# EEZ_DIB_PREL6_r1B1.net
KiCad netlist of a schematic drawn in EAGLE
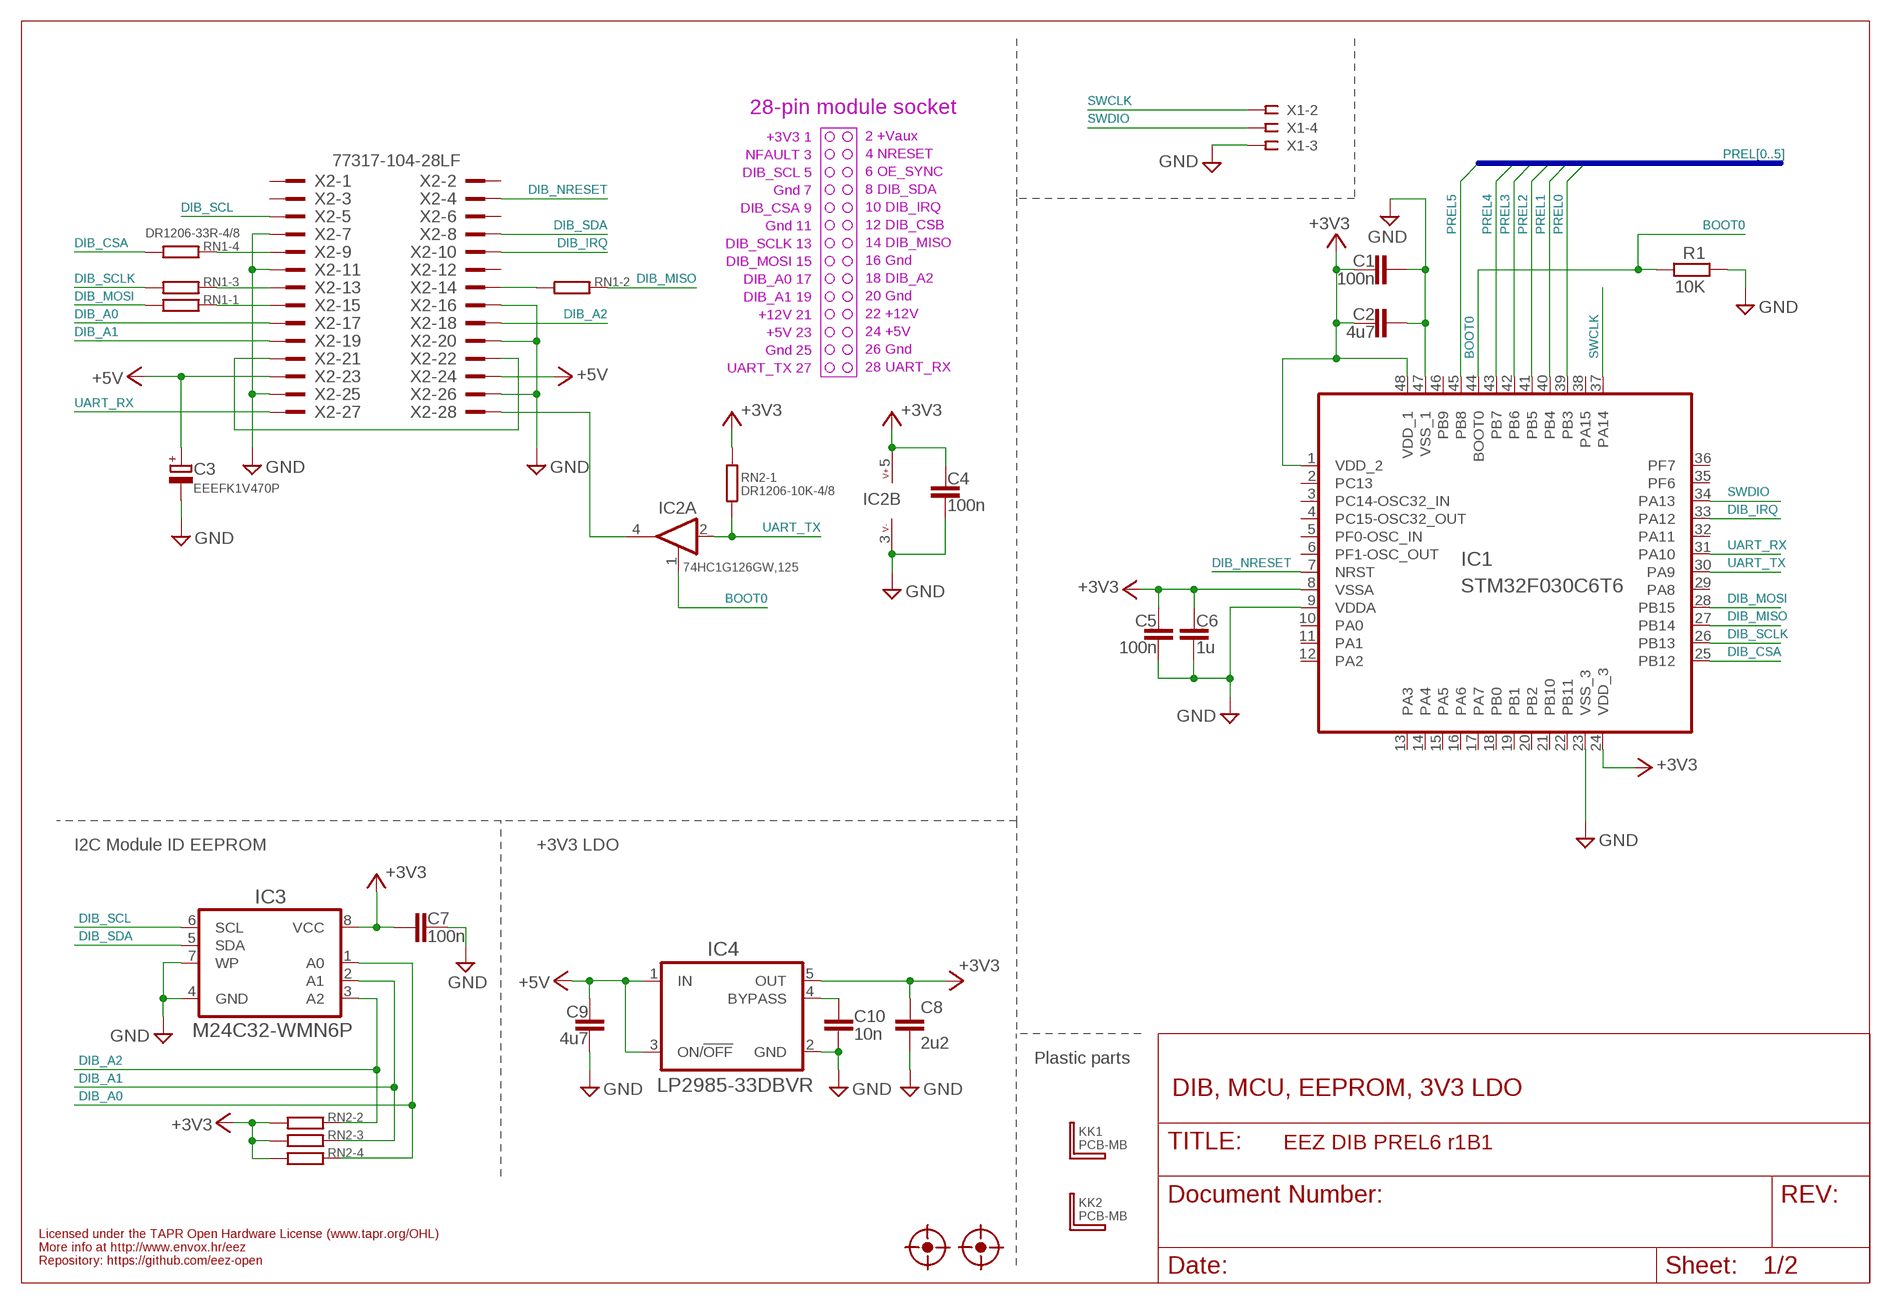
[diagram p0: schematic, sheet 1]
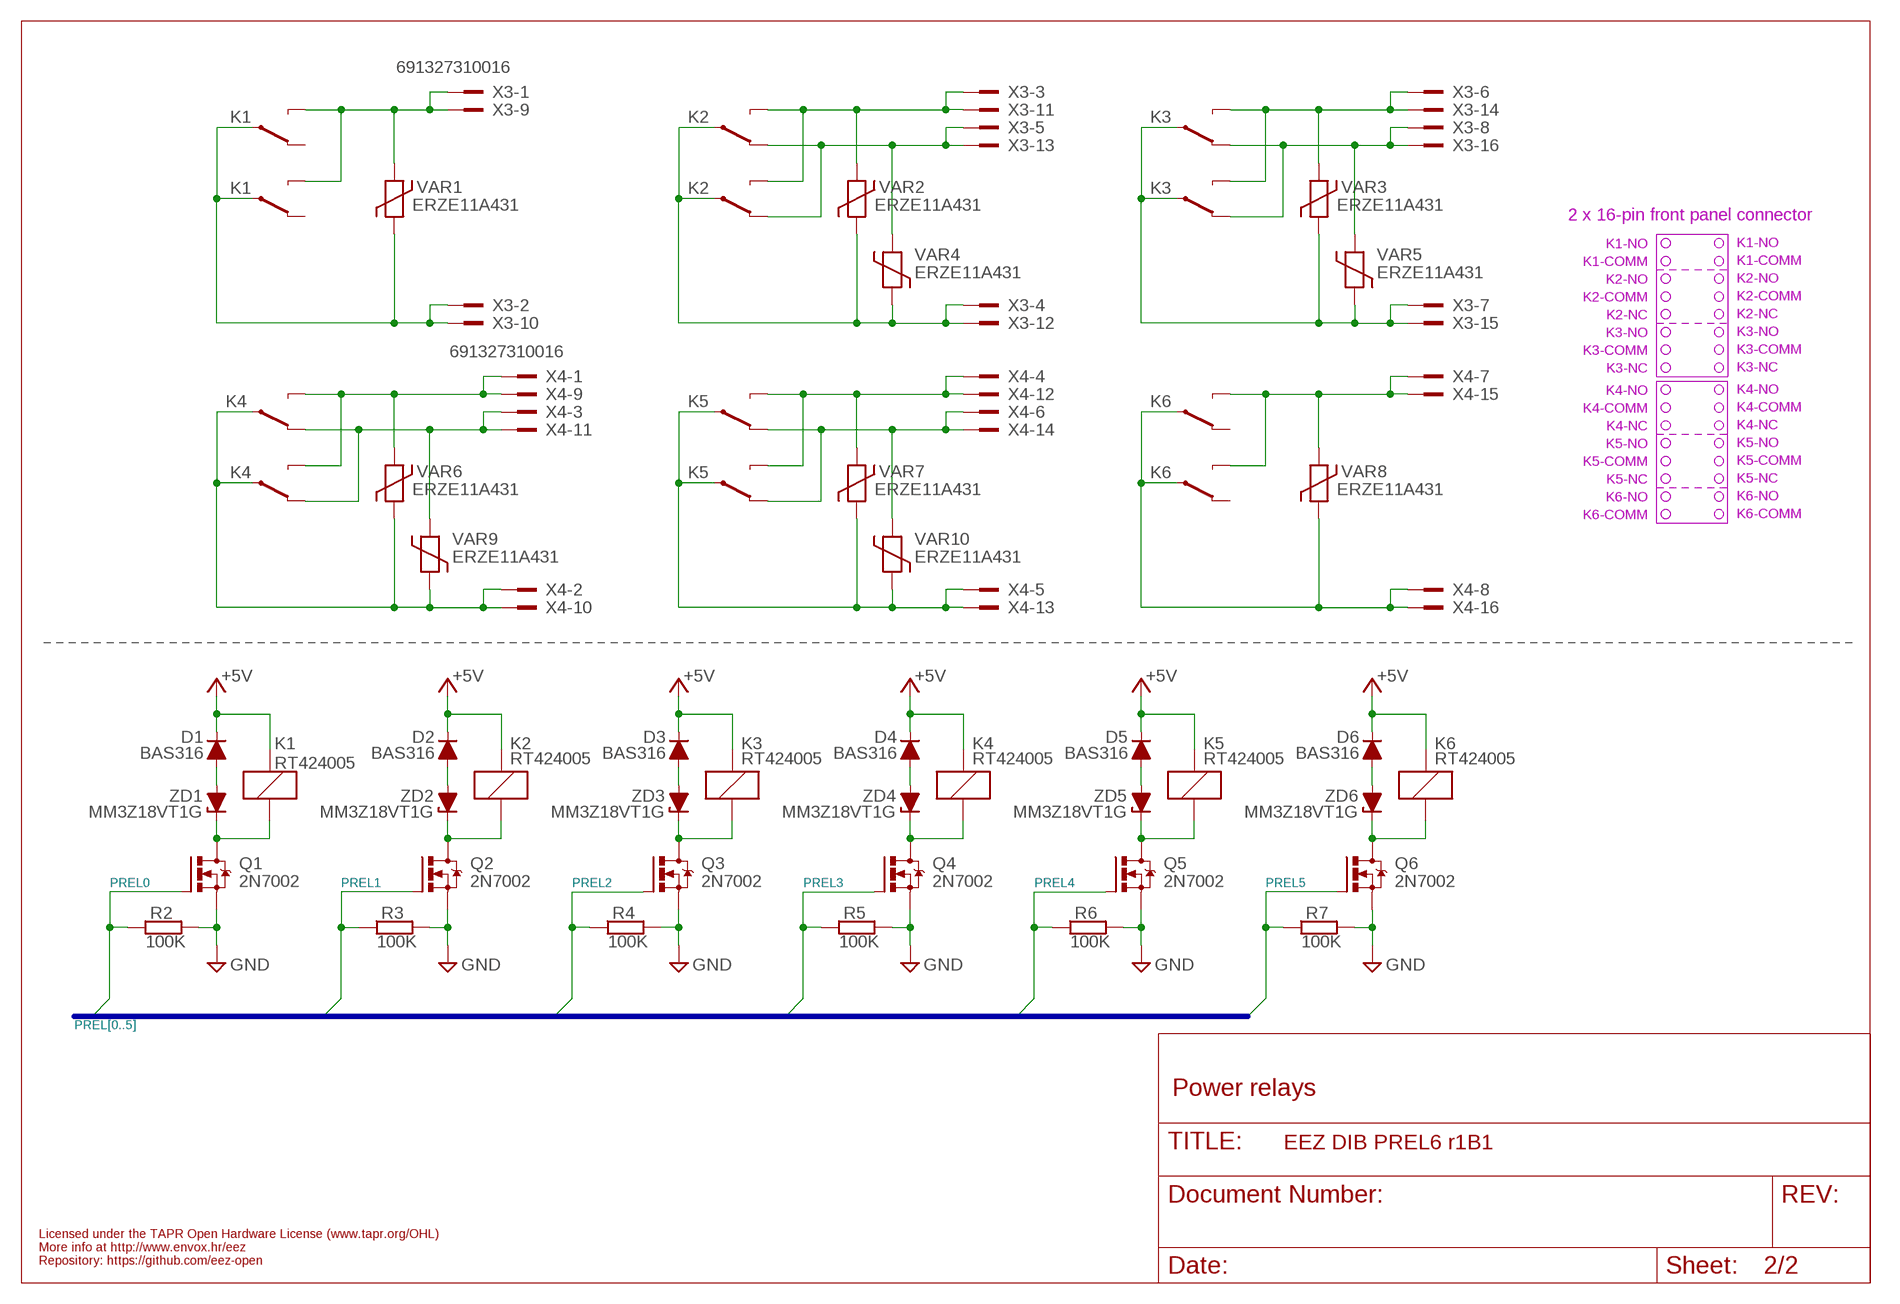
[diagram p1: schematic, sheet 2]

(export (version "E")
  (design (tool "Eeschema 10.0.6"))
  (components
    (comp (ref "D1")
      (value "BAS316")
      (footprint "eagle-import:SOD323-R")
      (libsource (lib "eagle-import") (part "DIODESOD323R"))
    )
    (comp (ref "D2")
      (value "BAS316")
      (footprint "eagle-import:SOD323-R")
      (libsource (lib "eagle-import") (part "DIODESOD323R"))
    )
    (comp (ref "D3")
      (value "BAS316")
      (footprint "eagle-import:SOD323-R")
      (libsource (lib "eagle-import") (part "DIODESOD323R"))
    )
    (comp (ref "D4")
      (value "BAS316")
      (footprint "eagle-import:SOD323-R")
      (libsource (lib "eagle-import") (part "DIODESOD323R"))
    )
    (comp (ref "D5")
      (value "BAS316")
      (footprint "eagle-import:SOD323-R")
      (libsource (lib "eagle-import") (part "DIODESOD323R"))
    )
    (comp (ref "D6")
      (value "BAS316")
      (footprint "eagle-import:SOD323-R")
      (libsource (lib "eagle-import") (part "DIODESOD323R"))
    )
    (comp (ref "K1")
      (value "RT424005")
      (footprint "eagle-import:RT-C_016A5_ROUND")
      (libsource (lib "eagle-import") (part "RELAY_RT314012-2"))
    )
    (comp (ref "K2")
      (value "RT424005")
      (footprint "eagle-import:RT-C_016A5_ROUND")
      (libsource (lib "eagle-import") (part "RELAY_RT314012-2"))
    )
    (comp (ref "K3")
      (value "RT424005")
      (footprint "eagle-import:RT-C_016A5_ROUND")
      (libsource (lib "eagle-import") (part "RELAY_RT314012-2"))
    )
    (comp (ref "K4")
      (value "RT424005")
      (footprint "eagle-import:RT-C_016A5_ROUND")
      (libsource (lib "eagle-import") (part "RELAY_RT314012-2"))
    )
    (comp (ref "K5")
      (value "RT424005")
      (footprint "eagle-import:RT-C_016A5_ROUND")
      (libsource (lib "eagle-import") (part "RELAY_RT314012-2"))
    )
    (comp (ref "K6")
      (value "RT424005")
      (footprint "eagle-import:RT-C_016A5_ROUND")
      (libsource (lib "eagle-import") (part "RELAY_RT314012-2"))
    )
    (comp (ref "Q1")
      (value "2N7002")
      (footprint "eagle-import:SOT103P240X110-3N")
      (fields
        (field (name "MPN") "2N7002-7-F")
        (field (name "MPN_1") "2N7002-7-F")
        (field (name "OC_FARNELL") "1713823")
        (field (name "OC_NEWARK") "25R5679")
        (field (name "PACKAGE") "SOT-23-3")
        (field (name "SUPPLIER") "DIODES INC.")
      )
      (libsource (lib "eagle-import") (part "2N7002"))
    )
    (comp (ref "Q2")
      (value "2N7002")
      (footprint "eagle-import:SOT103P240X110-3N")
      (fields
        (field (name "MPN") "2N7002-7-F")
        (field (name "MPN_1") "2N7002-7-F")
        (field (name "OC_FARNELL") "1713823")
        (field (name "OC_NEWARK") "25R5679")
        (field (name "PACKAGE") "SOT-23-3")
        (field (name "SUPPLIER") "DIODES INC.")
      )
      (libsource (lib "eagle-import") (part "2N7002"))
    )
    (comp (ref "Q3")
      (value "2N7002")
      (footprint "eagle-import:SOT103P240X110-3N")
      (fields
        (field (name "MPN") "2N7002-7-F")
        (field (name "MPN_1") "2N7002-7-F")
        (field (name "OC_FARNELL") "1713823")
        (field (name "OC_NEWARK") "25R5679")
        (field (name "PACKAGE") "SOT-23-3")
        (field (name "SUPPLIER") "DIODES INC.")
      )
      (libsource (lib "eagle-import") (part "2N7002"))
    )
    (comp (ref "Q4")
      (value "2N7002")
      (footprint "eagle-import:SOT103P240X110-3N")
      (fields
        (field (name "MPN") "2N7002-7-F")
        (field (name "MPN_1") "2N7002-7-F")
        (field (name "OC_FARNELL") "1713823")
        (field (name "OC_NEWARK") "25R5679")
        (field (name "PACKAGE") "SOT-23-3")
        (field (name "SUPPLIER") "DIODES INC.")
      )
      (libsource (lib "eagle-import") (part "2N7002"))
    )
    (comp (ref "Q5")
      (value "2N7002")
      (footprint "eagle-import:SOT103P240X110-3N")
      (fields
        (field (name "MPN") "2N7002-7-F")
        (field (name "MPN_1") "2N7002-7-F")
        (field (name "OC_FARNELL") "1713823")
        (field (name "OC_NEWARK") "25R5679")
        (field (name "PACKAGE") "SOT-23-3")
        (field (name "SUPPLIER") "DIODES INC.")
      )
      (libsource (lib "eagle-import") (part "2N7002"))
    )
    (comp (ref "Q6")
      (value "2N7002")
      (footprint "eagle-import:SOT103P240X110-3N")
      (fields
        (field (name "MPN") "2N7002-7-F")
        (field (name "MPN_1") "2N7002-7-F")
        (field (name "OC_FARNELL") "1713823")
        (field (name "OC_NEWARK") "25R5679")
        (field (name "PACKAGE") "SOT-23-3")
        (field (name "SUPPLIER") "DIODES INC.")
      )
      (libsource (lib "eagle-import") (part "2N7002"))
    )
    (comp (ref "R2")
      (value "100K")
      (footprint "eagle-import:R0805")
      (libsource (lib "eagle-import") (part "R-EU_R0805"))
    )
    (comp (ref "R3")
      (value "100K")
      (footprint "eagle-import:R0805")
      (libsource (lib "eagle-import") (part "R-EU_R0805"))
    )
    (comp (ref "R4")
      (value "100K")
      (footprint "eagle-import:R0805")
      (libsource (lib "eagle-import") (part "R-EU_R0805"))
    )
    (comp (ref "R5")
      (value "100K")
      (footprint "eagle-import:R0805")
      (libsource (lib "eagle-import") (part "R-EU_R0805"))
    )
    (comp (ref "R6")
      (value "100K")
      (footprint "eagle-import:R0805")
      (libsource (lib "eagle-import") (part "R-EU_R0805"))
    )
    (comp (ref "R7")
      (value "100K")
      (footprint "eagle-import:R0805")
      (libsource (lib "eagle-import") (part "R-EU_R0805"))
    )
    (comp (ref "VAR1")
      (value "ERZE11A431")
      (footprint "eagle-import:VARISTOR_13MM")
      (libsource (lib "eagle-import") (part "VARISTOR-13"))
    )
    (comp (ref "VAR2")
      (value "ERZE11A431")
      (footprint "eagle-import:VARISTOR_13MM")
      (libsource (lib "eagle-import") (part "VARISTOR-13"))
    )
    (comp (ref "VAR3")
      (value "ERZE11A431")
      (footprint "eagle-import:VARISTOR_13MM")
      (libsource (lib "eagle-import") (part "VARISTOR-13"))
    )
    (comp (ref "VAR4")
      (value "ERZE11A431")
      (footprint "eagle-import:VARISTOR_13MM")
      (libsource (lib "eagle-import") (part "VARISTOR-13"))
    )
    (comp (ref "VAR5")
      (value "ERZE11A431")
      (footprint "eagle-import:VARISTOR_13MM")
      (libsource (lib "eagle-import") (part "VARISTOR-13"))
    )
    (comp (ref "VAR6")
      (value "ERZE11A431")
      (footprint "eagle-import:VARISTOR_13MM")
      (libsource (lib "eagle-import") (part "VARISTOR-13"))
    )
    (comp (ref "VAR7")
      (value "ERZE11A431")
      (footprint "eagle-import:VARISTOR_13MM")
      (libsource (lib "eagle-import") (part "VARISTOR-13"))
    )
    (comp (ref "VAR8")
      (value "ERZE11A431")
      (footprint "eagle-import:VARISTOR_13MM")
      (libsource (lib "eagle-import") (part "VARISTOR-13"))
    )
    (comp (ref "VAR9")
      (value "ERZE11A431")
      (footprint "eagle-import:VARISTOR_13MM")
      (libsource (lib "eagle-import") (part "VARISTOR-13"))
    )
    (comp (ref "VAR10")
      (value "ERZE11A431")
      (footprint "eagle-import:VARISTOR_13MM")
      (libsource (lib "eagle-import") (part "VARISTOR-13"))
    )
    (comp (ref "X3")
      (value "691327310016")
      (footprint "eagle-import:691327310016")
      (libsource (lib "eagle-import") (part "691327310016"))
    )
    (comp (ref "X4")
      (value "691327310016")
      (footprint "eagle-import:691327310016")
      (libsource (lib "eagle-import") (part "691327310016"))
    )
    (comp (ref "ZD1")
      (value "MM3Z18VT1G")
      (footprint "eagle-import:SOD323-R")
      (libsource (lib "eagle-import") (part "ZENER-DIODESOD323R"))
    )
    (comp (ref "ZD2")
      (value "MM3Z18VT1G")
      (footprint "eagle-import:SOD323-R")
      (libsource (lib "eagle-import") (part "ZENER-DIODESOD323R"))
    )
    (comp (ref "ZD3")
      (value "MM3Z18VT1G")
      (footprint "eagle-import:SOD323-R")
      (libsource (lib "eagle-import") (part "ZENER-DIODESOD323R"))
    )
    (comp (ref "ZD4")
      (value "MM3Z18VT1G")
      (footprint "eagle-import:SOD323-R")
      (libsource (lib "eagle-import") (part "ZENER-DIODESOD323R"))
    )
    (comp (ref "ZD5")
      (value "MM3Z18VT1G")
      (footprint "eagle-import:SOD323-R")
      (libsource (lib "eagle-import") (part "ZENER-DIODESOD323R"))
    )
    (comp (ref "ZD6")
      (value "MM3Z18VT1G")
      (footprint "eagle-import:SOD323-R")
      (libsource (lib "eagle-import") (part "ZENER-DIODESOD323R"))
    )
    (comp (ref "C1")
      (value "100n")
      (footprint "eagle-import:C0603")
      (libsource (lib "eagle-import") (part "C-EUC0603"))
    )
    (comp (ref "C2")
      (value "4u7")
      (footprint "eagle-import:C1206")
      (libsource (lib "eagle-import") (part "C-EUC1206"))
    )
    (comp (ref "C3")
      (value "EEEFK1V470P")
      (footprint "eagle-import:CAPAE660X610N")
      (libsource (lib "eagle-import") (part "ECAPPANASONIC_H"))
    )
    (comp (ref "C4")
      (value "100n")
      (footprint "eagle-import:C0603")
      (libsource (lib "eagle-import") (part "C-EUC0603"))
    )
    (comp (ref "C5")
      (value "100n")
      (footprint "eagle-import:C0603")
      (libsource (lib "eagle-import") (part "C-EUC0603"))
    )
    (comp (ref "C6")
      (value "1u")
      (footprint "eagle-import:C0805")
      (libsource (lib "eagle-import") (part "C-EUC0805"))
    )
    (comp (ref "C7")
      (value "100n")
      (footprint "eagle-import:C0603")
      (libsource (lib "eagle-import") (part "C-EUC0603"))
    )
    (comp (ref "C8")
      (value "2u2")
      (footprint "eagle-import:C1206")
      (libsource (lib "eagle-import") (part "C-EUC1206"))
    )
    (comp (ref "C9")
      (value "4u7")
      (footprint "eagle-import:C1206")
      (libsource (lib "eagle-import") (part "C-EUC1206"))
    )
    (comp (ref "C10")
      (value "10n")
      (footprint "eagle-import:C0805")
      (libsource (lib "eagle-import") (part "C-EUC0805"))
    )
    (comp (ref "FM1")
      (value "FIDUCIAL_2")
      (footprint "eagle-import:FIDUCIAL_DUAL")
      (libsource (lib "eagle-import") (part "FIDUCIAL_2"))
    )
    (comp (ref "FM2")
      (value "FIDUCIAL_2")
      (footprint "eagle-import:FIDUCIAL_DUAL")
      (libsource (lib "eagle-import") (part "FIDUCIAL_2"))
    )
    (comp (ref "IC1")
      (value "STM32F030C6T6")
      (footprint "eagle-import:LQFP-48")
      (libsource (lib "eagle-import") (part "STM32F030C6T6"))
    )
    (comp (ref "IC2")
      (value "74HC1G126GW,125")
      (footprint "eagle-import:SOT65P210X110-5N")
      (libsource (lib "eagle-import") (part "74HC1G126GW,125"))
    )
    (comp (ref "IC3")
      (value "M24C32-WMN6P")
      (footprint "eagle-import:SOIC127P600X173-8N")
      (libsource (lib "eagle-import") (part "AT24CXXSOIC8"))
    )
    (comp (ref "IC4")
      (value "LP2985-33DBVR")
      (footprint "eagle-import:SOT95P270X145-5N")
      (libsource (lib "eagle-import") (part "LP2985"))
    )
    (comp (ref "KK1")
      (value "PCB-MB")
      (footprint "eagle-import:PCB-MB")
      (libsource (lib "eagle-import") (part "PCB-MB"))
    )
    (comp (ref "KK2")
      (value "PCB-MB")
      (footprint "eagle-import:PCB-MB")
      (libsource (lib "eagle-import") (part "PCB-MB"))
    )
    (comp (ref "R1")
      (value "10K")
      (footprint "eagle-import:R0805")
      (libsource (lib "eagle-import") (part "R-EU_R0805"))
    )
    (comp (ref "RN1")
      (value "DR1206-33R-4/8")
      (footprint "eagle-import:CAY16")
      (libsource (lib "eagle-import") (part "R_ARRAY4"))
    )
    (comp (ref "RN2")
      (value "DR1206-10K-4/8")
      (footprint "eagle-import:CAY16")
      (libsource (lib "eagle-import") (part "R_ARRAY4"))
    )
    (comp (ref "X1")
      (value "SSW-106-02-S-S")
      (footprint "eagle-import:SSW-106-02-S-S")
      (libsource (lib "eagle-import") (part "SSW-106-02-S-S"))
    )
    (comp (ref "X2")
      (value "77317-104-28LF")
      (footprint "eagle-import:77317-104-28LF")
      (libsource (lib "eagle-import") (part "77317-104-28LF"))
    )
  )
  (nets
    (net (code "1") (name "+3V3") (class "Default")
      (node (ref "C1") (pin "2") (pinfunction "2_2") (pintype "passive"))
      (node (ref "C2") (pin "1") (pinfunction "1_1") (pintype "passive"))
      (node (ref "C4") (pin "1") (pinfunction "1_1") (pintype "passive"))
      (node (ref "C5") (pin "1") (pinfunction "1_1") (pintype "passive"))
      (node (ref "C6") (pin "2") (pinfunction "2_2") (pintype "passive"))
      (node (ref "C7") (pin "2") (pinfunction "2_2") (pintype "passive"))
      (node (ref "C8") (pin "1") (pinfunction "1_1") (pintype "passive"))
      (node (ref "IC1") (pin "1") (pinfunction "VDD_2_1") (pintype "passive"))
      (node (ref "IC1") (pin "24") (pinfunction "VDD_3_24") (pintype "passive"))
      (node (ref "IC1") (pin "48") (pinfunction "VDD_1_48") (pintype "passive"))
      (node (ref "IC1") (pin "8") (pinfunction "VSSA_8") (pintype "passive"))
      (node (ref "IC2") (pin "5") (pinfunction "V+_5") (pintype "power_in"))
      (node (ref "IC3") (pin "8") (pinfunction "VCC_8") (pintype "power_in"))
      (node (ref "IC4") (pin "5") (pinfunction "OUT_5") (pintype "passive"))
      (node (ref "RN2") (pin "5") (pinfunction "2_5") (pintype "passive"))
      (node (ref "RN2") (pin "6") (pinfunction "2_6") (pintype "passive"))
      (node (ref "RN2") (pin "7") (pinfunction "2_7") (pintype "passive"))
      (node (ref "RN2") (pin "8") (pinfunction "2_8") (pintype "passive"))
    )
    (net (code "2") (name "+5V") (class "Default")
      (node (ref "C3") (pin "1") (pinfunction "+_1") (pintype "passive"))
      (node (ref "C9") (pin "2") (pinfunction "2_2") (pintype "passive"))
      (node (ref "D1") (pin "C") (pinfunction "C_C") (pintype "passive"))
      (node (ref "D2") (pin "C") (pinfunction "C_C") (pintype "passive"))
      (node (ref "D3") (pin "C") (pinfunction "C_C") (pintype "passive"))
      (node (ref "D4") (pin "C") (pinfunction "C_C") (pintype "passive"))
      (node (ref "D5") (pin "C") (pinfunction "C_C") (pintype "passive"))
      (node (ref "D6") (pin "C") (pinfunction "C_C") (pintype "passive"))
      (node (ref "IC4") (pin "1") (pinfunction "IN_1") (pintype "input"))
      (node (ref "IC4") (pin "3") (pinfunction "ON/~{OFF}_3") (pintype "input"))
      (node (ref "K1") (pin "A2") (pinfunction "C1_A2") (pintype "passive"))
      (node (ref "K2") (pin "A2") (pinfunction "C1_A2") (pintype "passive"))
      (node (ref "K3") (pin "A2") (pinfunction "C1_A2") (pintype "passive"))
      (node (ref "K4") (pin "A2") (pinfunction "C1_A2") (pintype "passive"))
      (node (ref "K5") (pin "A2") (pinfunction "C1_A2") (pintype "passive"))
      (node (ref "K6") (pin "A2") (pinfunction "C1_A2") (pintype "passive"))
      (node (ref "X2") (pin "23") (pinfunction "1_23") (pintype "passive"))
      (node (ref "X2") (pin "24") (pinfunction "1_24") (pintype "passive"))
    )
    (net (code "5") (name "BOOT0") (class "Default")
      (node (ref "IC1") (pin "44") (pinfunction "BOOT0_44") (pintype "input"))
      (node (ref "IC2") (pin "1") (pinfunction "EN_1") (pintype "input"))
      (node (ref "R1") (pin "2") (pinfunction "2_2") (pintype "passive"))
    )
    (net (code "6") (name "DIB_A0") (class "Default")
      (node (ref "IC3") (pin "1") (pinfunction "A0_1") (pintype "input"))
      (node (ref "RN2") (pin "4") (pinfunction "1_4") (pintype "passive"))
      (node (ref "X2") (pin "17") (pinfunction "1_17") (pintype "passive"))
    )
    (net (code "7") (name "DIB_A1") (class "Default")
      (node (ref "IC3") (pin "2") (pinfunction "A1_2") (pintype "input"))
      (node (ref "RN2") (pin "3") (pinfunction "1_3") (pintype "passive"))
      (node (ref "X2") (pin "19") (pinfunction "1_19") (pintype "passive"))
    )
    (net (code "8") (name "DIB_A2") (class "Default")
      (node (ref "IC3") (pin "3") (pinfunction "A2_3") (pintype "input"))
      (node (ref "RN2") (pin "2") (pinfunction "1_2") (pintype "passive"))
      (node (ref "X2") (pin "18") (pinfunction "1_18") (pintype "passive"))
    )
    (net (code "9") (name "DIB_CSA") (class "Default")
      (node (ref "IC1") (pin "25") (pinfunction "PB12_25") (pintype "bidirectional"))
      (node (ref "RN1") (pin "4") (pinfunction "1_4") (pintype "passive"))
    )
    (net (code "10") (name "DIB_IRQ") (class "Default")
      (node (ref "IC1") (pin "33") (pinfunction "PA12_33") (pintype "bidirectional"))
      (node (ref "X2") (pin "10") (pinfunction "1_10") (pintype "passive"))
    )
    (net (code "11") (name "DIB_MISO") (class "Default")
      (node (ref "IC1") (pin "27") (pinfunction "PB14_27") (pintype "bidirectional"))
      (node (ref "RN1") (pin "2") (pinfunction "1_2") (pintype "passive"))
    )
    (net (code "12") (name "DIB_MOSI") (class "Default")
      (node (ref "IC1") (pin "28") (pinfunction "PB15_28") (pintype "bidirectional"))
      (node (ref "RN1") (pin "1") (pinfunction "1_1") (pintype "passive"))
    )
    (net (code "13") (name "DIB_NRESET") (class "Default")
      (node (ref "IC1") (pin "7") (pinfunction "NRST_7") (pintype "input"))
      (node (ref "X2") (pin "4") (pinfunction "1_4") (pintype "passive"))
    )
    (net (code "14") (name "DIB_SCL") (class "Default")
      (node (ref "IC3") (pin "6") (pinfunction "SCL_6") (pintype "bidirectional"))
      (node (ref "X2") (pin "5") (pinfunction "1_5") (pintype "passive"))
    )
    (net (code "15") (name "DIB_SCLK") (class "Default")
      (node (ref "IC1") (pin "26") (pinfunction "PB13_26") (pintype "bidirectional"))
      (node (ref "RN1") (pin "3") (pinfunction "1_3") (pintype "passive"))
    )
    (net (code "16") (name "DIB_SDA") (class "Default")
      (node (ref "IC3") (pin "5") (pinfunction "SDA_5") (pintype "bidirectional"))
      (node (ref "X2") (pin "8") (pinfunction "1_8") (pintype "passive"))
    )
    (net (code "17") (name "GND") (class "Default")
      (node (ref "C1") (pin "1") (pinfunction "1_1") (pintype "passive"))
      (node (ref "C10") (pin "1") (pinfunction "1_1") (pintype "passive"))
      (node (ref "C2") (pin "2") (pinfunction "2_2") (pintype "passive"))
      (node (ref "C3") (pin "2") (pinfunction "-_2") (pintype "passive"))
      (node (ref "C4") (pin "2") (pinfunction "2_2") (pintype "passive"))
      (node (ref "C5") (pin "2") (pinfunction "2_2") (pintype "passive"))
      (node (ref "C6") (pin "1") (pinfunction "1_1") (pintype "passive"))
      (node (ref "C7") (pin "1") (pinfunction "1_1") (pintype "passive"))
      (node (ref "C8") (pin "2") (pinfunction "2_2") (pintype "passive"))
      (node (ref "C9") (pin "1") (pinfunction "1_1") (pintype "passive"))
      (node (ref "IC1") (pin "23") (pinfunction "VSS_3_23") (pintype "passive"))
      (node (ref "IC1") (pin "47") (pinfunction "VSS_1_47") (pintype "passive"))
      (node (ref "IC1") (pin "9") (pinfunction "VDDA_9") (pintype "passive"))
      (node (ref "IC2") (pin "3") (pinfunction "V-_3") (pintype "power_in"))
      (node (ref "IC3") (pin "4") (pinfunction "GND_4") (pintype "passive"))
      (node (ref "IC3") (pin "7") (pinfunction "WP_7") (pintype "input"))
      (node (ref "IC4") (pin "2") (pinfunction "GND_2") (pintype "passive"))
      (node (ref "Q1") (pin "2") (pinfunction "S_2") (pintype "passive"))
      (node (ref "Q2") (pin "2") (pinfunction "S_2") (pintype "passive"))
      (node (ref "Q3") (pin "2") (pinfunction "S_2") (pintype "passive"))
      (node (ref "Q4") (pin "2") (pinfunction "S_2") (pintype "passive"))
      (node (ref "Q5") (pin "2") (pinfunction "S_2") (pintype "passive"))
      (node (ref "Q6") (pin "2") (pinfunction "S_2") (pintype "passive"))
      (node (ref "R1") (pin "1") (pinfunction "1_1") (pintype "passive"))
      (node (ref "R2") (pin "2") (pinfunction "2_2") (pintype "passive"))
      (node (ref "R3") (pin "2") (pinfunction "2_2") (pintype "passive"))
      (node (ref "R4") (pin "2") (pinfunction "2_2") (pintype "passive"))
      (node (ref "R5") (pin "2") (pinfunction "2_2") (pintype "passive"))
      (node (ref "R6") (pin "2") (pinfunction "2_2") (pintype "passive"))
      (node (ref "R7") (pin "2") (pinfunction "2_2") (pintype "passive"))
      (node (ref "X1") (pin "3") (pinfunction "1_3") (pintype "passive"))
      (node (ref "X2") (pin "11") (pinfunction "1_11") (pintype "passive"))
      (node (ref "X2") (pin "16") (pinfunction "1_16") (pintype "passive"))
      (node (ref "X2") (pin "20") (pinfunction "1_20") (pintype "passive"))
      (node (ref "X2") (pin "25") (pinfunction "1_25") (pintype "passive"))
      (node (ref "X2") (pin "26") (pinfunction "1_26") (pintype "passive"))
      (node (ref "X2") (pin "7") (pinfunction "1_7") (pintype "passive"))
    )
    (net (code "18") (name "Net-(D1-PadA)") (class "Default")
      (node (ref "D1") (pin "A") (pinfunction "A_A") (pintype "passive"))
      (node (ref "ZD1") (pin "A") (pinfunction "A_A") (pintype "passive"))
    )
    (net (code "19") (name "Net-(D2-PadA)") (class "Default")
      (node (ref "D2") (pin "A") (pinfunction "A_A") (pintype "passive"))
      (node (ref "ZD2") (pin "A") (pinfunction "A_A") (pintype "passive"))
    )
    (net (code "20") (name "Net-(D3-PadA)") (class "Default")
      (node (ref "D3") (pin "A") (pinfunction "A_A") (pintype "passive"))
      (node (ref "ZD3") (pin "A") (pinfunction "A_A") (pintype "passive"))
    )
    (net (code "21") (name "Net-(D4-PadA)") (class "Default")
      (node (ref "D4") (pin "A") (pinfunction "A_A") (pintype "passive"))
      (node (ref "ZD4") (pin "A") (pinfunction "A_A") (pintype "passive"))
    )
    (net (code "22") (name "Net-(D5-PadA)") (class "Default")
      (node (ref "D5") (pin "A") (pinfunction "A_A") (pintype "passive"))
      (node (ref "ZD5") (pin "A") (pinfunction "A_A") (pintype "passive"))
    )
    (net (code "23") (name "Net-(D6-PadA)") (class "Default")
      (node (ref "D6") (pin "A") (pinfunction "A_A") (pintype "passive"))
      (node (ref "ZD6") (pin "A") (pinfunction "A_A") (pintype "passive"))
    )
    (net (code "24") (name "Net-(IC2A-O)") (class "Default")
      (node (ref "IC2") (pin "4") (pinfunction "O_4") (pintype "output"))
      (node (ref "X2") (pin "28") (pinfunction "1_28") (pintype "passive"))
    )
    (net (code "25") (name "Net-(IC4-BYPASS)") (class "Default")
      (node (ref "C10") (pin "2") (pinfunction "2_2") (pintype "passive"))
      (node (ref "IC4") (pin "4") (pinfunction "BYPASS_4") (pintype "passive"))
    )
    (net (code "26") (name "Net-(K1A-O)") (class "Default")
      (node (ref "K1") (pin "14A") (pinfunction "O_14A") (pintype "passive"))
      (node (ref "K1") (pin "14B") (pinfunction "O_14B") (pintype "passive"))
      (node (ref "VAR1") (pin "2") (pinfunction "P$2_2") (pintype "bidirectional"))
      (node (ref "X3") (pin "1") (pinfunction "1_1") (pintype "passive"))
      (node (ref "X3") (pin "9") (pinfunction "1_9") (pintype "passive"))
    )
    (net (code "27") (name "Net-(K1A-P)") (class "Default")
      (node (ref "K1") (pin "11A") (pinfunction "P_11A") (pintype "passive"))
      (node (ref "K1") (pin "11B") (pinfunction "P_11B") (pintype "passive"))
      (node (ref "VAR1") (pin "1") (pinfunction "P$1_1") (pintype "bidirectional"))
      (node (ref "X3") (pin "10") (pinfunction "1_10") (pintype "passive"))
      (node (ref "X3") (pin "2") (pinfunction "1_2") (pintype "passive"))
    )
    (net (code "28") (name "Net-(K1C-C2)") (class "Default")
      (node (ref "K1") (pin "A1") (pinfunction "C2_A1") (pintype "passive"))
      (node (ref "Q1") (pin "3") (pinfunction "D_3") (pintype "passive"))
      (node (ref "ZD1") (pin "C") (pinfunction "C_C") (pintype "passive"))
    )
    (net (code "29") (name "Net-(K2A-O)") (class "Default")
      (node (ref "K2") (pin "14A") (pinfunction "O_14A") (pintype "passive"))
      (node (ref "K2") (pin "14B") (pinfunction "O_14B") (pintype "passive"))
      (node (ref "VAR2") (pin "2") (pinfunction "P$2_2") (pintype "bidirectional"))
      (node (ref "X3") (pin "11") (pinfunction "1_11") (pintype "passive"))
      (node (ref "X3") (pin "3") (pinfunction "1_3") (pintype "passive"))
    )
    (net (code "30") (name "Net-(K2A-P)") (class "Default")
      (node (ref "K2") (pin "11A") (pinfunction "P_11A") (pintype "passive"))
      (node (ref "K2") (pin "11B") (pinfunction "P_11B") (pintype "passive"))
      (node (ref "VAR2") (pin "1") (pinfunction "P$1_1") (pintype "bidirectional"))
      (node (ref "VAR4") (pin "1") (pinfunction "P$1_1") (pintype "bidirectional"))
      (node (ref "X3") (pin "12") (pinfunction "1_12") (pintype "passive"))
      (node (ref "X3") (pin "4") (pinfunction "1_4") (pintype "passive"))
    )
    (net (code "31") (name "Net-(K2A-S)") (class "Default")
      (node (ref "K2") (pin "12A") (pinfunction "S_12A") (pintype "passive"))
      (node (ref "K2") (pin "12B") (pinfunction "S_12B") (pintype "passive"))
      (node (ref "VAR4") (pin "2") (pinfunction "P$2_2") (pintype "bidirectional"))
      (node (ref "X3") (pin "13") (pinfunction "1_13") (pintype "passive"))
      (node (ref "X3") (pin "5") (pinfunction "1_5") (pintype "passive"))
    )
    (net (code "32") (name "Net-(K2C-C2)") (class "Default")
      (node (ref "K2") (pin "A1") (pinfunction "C2_A1") (pintype "passive"))
      (node (ref "Q2") (pin "3") (pinfunction "D_3") (pintype "passive"))
      (node (ref "ZD2") (pin "C") (pinfunction "C_C") (pintype "passive"))
    )
    (net (code "33") (name "Net-(K3A-O)") (class "Default")
      (node (ref "K3") (pin "14A") (pinfunction "O_14A") (pintype "passive"))
      (node (ref "K3") (pin "14B") (pinfunction "O_14B") (pintype "passive"))
      (node (ref "VAR3") (pin "2") (pinfunction "P$2_2") (pintype "bidirectional"))
      (node (ref "X3") (pin "14") (pinfunction "1_14") (pintype "passive"))
      (node (ref "X3") (pin "6") (pinfunction "1_6") (pintype "passive"))
    )
    (net (code "34") (name "Net-(K3A-P)") (class "Default")
      (node (ref "K3") (pin "11A") (pinfunction "P_11A") (pintype "passive"))
      (node (ref "K3") (pin "11B") (pinfunction "P_11B") (pintype "passive"))
      (node (ref "VAR3") (pin "1") (pinfunction "P$1_1") (pintype "bidirectional"))
      (node (ref "VAR5") (pin "1") (pinfunction "P$1_1") (pintype "bidirectional"))
      (node (ref "X3") (pin "15") (pinfunction "1_15") (pintype "passive"))
      (node (ref "X3") (pin "7") (pinfunction "1_7") (pintype "passive"))
    )
    (net (code "35") (name "Net-(K3A-S)") (class "Default")
      (node (ref "K3") (pin "12A") (pinfunction "S_12A") (pintype "passive"))
      (node (ref "K3") (pin "12B") (pinfunction "S_12B") (pintype "passive"))
      (node (ref "VAR5") (pin "2") (pinfunction "P$2_2") (pintype "bidirectional"))
      (node (ref "X3") (pin "16") (pinfunction "1_16") (pintype "passive"))
      (node (ref "X3") (pin "8") (pinfunction "1_8") (pintype "passive"))
    )
    (net (code "36") (name "Net-(K3C-C2)") (class "Default")
      (node (ref "K3") (pin "A1") (pinfunction "C2_A1") (pintype "passive"))
      (node (ref "Q3") (pin "3") (pinfunction "D_3") (pintype "passive"))
      (node (ref "ZD3") (pin "C") (pinfunction "C_C") (pintype "passive"))
    )
    (net (code "37") (name "Net-(K4A-O)") (class "Default")
      (node (ref "K4") (pin "14A") (pinfunction "O_14A") (pintype "passive"))
      (node (ref "K4") (pin "14B") (pinfunction "O_14B") (pintype "passive"))
      (node (ref "VAR6") (pin "2") (pinfunction "P$2_2") (pintype "bidirectional"))
      (node (ref "X4") (pin "1") (pinfunction "1_1") (pintype "passive"))
      (node (ref "X4") (pin "9") (pinfunction "1_9") (pintype "passive"))
    )
    (net (code "38") (name "Net-(K4A-P)") (class "Default")
      (node (ref "K4") (pin "11A") (pinfunction "P_11A") (pintype "passive"))
      (node (ref "K4") (pin "11B") (pinfunction "P_11B") (pintype "passive"))
      (node (ref "VAR6") (pin "1") (pinfunction "P$1_1") (pintype "bidirectional"))
      (node (ref "VAR9") (pin "1") (pinfunction "P$1_1") (pintype "bidirectional"))
      (node (ref "X4") (pin "10") (pinfunction "1_10") (pintype "passive"))
      (node (ref "X4") (pin "2") (pinfunction "1_2") (pintype "passive"))
    )
    (net (code "39") (name "Net-(K4A-S)") (class "Default")
      (node (ref "K4") (pin "12A") (pinfunction "S_12A") (pintype "passive"))
      (node (ref "K4") (pin "12B") (pinfunction "S_12B") (pintype "passive"))
      (node (ref "VAR9") (pin "2") (pinfunction "P$2_2") (pintype "bidirectional"))
      (node (ref "X4") (pin "11") (pinfunction "1_11") (pintype "passive"))
      (node (ref "X4") (pin "3") (pinfunction "1_3") (pintype "passive"))
    )
    (net (code "40") (name "Net-(K4C-C2)") (class "Default")
      (node (ref "K4") (pin "A1") (pinfunction "C2_A1") (pintype "passive"))
      (node (ref "Q4") (pin "3") (pinfunction "D_3") (pintype "passive"))
      (node (ref "ZD4") (pin "C") (pinfunction "C_C") (pintype "passive"))
    )
    (net (code "41") (name "Net-(K5A-O)") (class "Default")
      (node (ref "K5") (pin "14A") (pinfunction "O_14A") (pintype "passive"))
      (node (ref "K5") (pin "14B") (pinfunction "O_14B") (pintype "passive"))
      (node (ref "VAR7") (pin "2") (pinfunction "P$2_2") (pintype "bidirectional"))
      (node (ref "X4") (pin "12") (pinfunction "1_12") (pintype "passive"))
      (node (ref "X4") (pin "4") (pinfunction "1_4") (pintype "passive"))
    )
    (net (code "42") (name "Net-(K5A-P)") (class "Default")
      (node (ref "K5") (pin "11A") (pinfunction "P_11A") (pintype "passive"))
      (node (ref "K5") (pin "11B") (pinfunction "P_11B") (pintype "passive"))
      (node (ref "VAR10") (pin "1") (pinfunction "P$1_1") (pintype "bidirectional"))
      (node (ref "VAR7") (pin "1") (pinfunction "P$1_1") (pintype "bidirectional"))
      (node (ref "X4") (pin "13") (pinfunction "1_13") (pintype "passive"))
      (node (ref "X4") (pin "5") (pinfunction "1_5") (pintype "passive"))
    )
    (net (code "43") (name "Net-(K5A-S)") (class "Default")
      (node (ref "K5") (pin "12A") (pinfunction "S_12A") (pintype "passive"))
      (node (ref "K5") (pin "12B") (pinfunction "S_12B") (pintype "passive"))
      (node (ref "VAR10") (pin "2") (pinfunction "P$2_2") (pintype "bidirectional"))
      (node (ref "X4") (pin "14") (pinfunction "1_14") (pintype "passive"))
      (node (ref "X4") (pin "6") (pinfunction "1_6") (pintype "passive"))
    )
    (net (code "44") (name "Net-(K5C-C2)") (class "Default")
      (node (ref "K5") (pin "A1") (pinfunction "C2_A1") (pintype "passive"))
      (node (ref "Q5") (pin "3") (pinfunction "D_3") (pintype "passive"))
      (node (ref "ZD5") (pin "C") (pinfunction "C_C") (pintype "passive"))
    )
    (net (code "45") (name "Net-(K6A-O)") (class "Default")
      (node (ref "K6") (pin "14A") (pinfunction "O_14A") (pintype "passive"))
      (node (ref "K6") (pin "14B") (pinfunction "O_14B") (pintype "passive"))
      (node (ref "VAR8") (pin "2") (pinfunction "P$2_2") (pintype "bidirectional"))
      (node (ref "X4") (pin "15") (pinfunction "1_15") (pintype "passive"))
      (node (ref "X4") (pin "7") (pinfunction "1_7") (pintype "passive"))
    )
    (net (code "46") (name "Net-(K6A-P)") (class "Default")
      (node (ref "K6") (pin "11A") (pinfunction "P_11A") (pintype "passive"))
      (node (ref "K6") (pin "11B") (pinfunction "P_11B") (pintype "passive"))
      (node (ref "VAR8") (pin "1") (pinfunction "P$1_1") (pintype "bidirectional"))
      (node (ref "X4") (pin "16") (pinfunction "1_16") (pintype "passive"))
      (node (ref "X4") (pin "8") (pinfunction "1_8") (pintype "passive"))
    )
    (net (code "47") (name "Net-(K6C-C2)") (class "Default")
      (node (ref "K6") (pin "A1") (pinfunction "C2_A1") (pintype "passive"))
      (node (ref "Q6") (pin "3") (pinfunction "D_3") (pintype "passive"))
      (node (ref "ZD6") (pin "C") (pinfunction "C_C") (pintype "passive"))
    )
    (net (code "48") (name "Net-(RN1A-2)") (class "Default")
      (node (ref "RN1") (pin "8") (pinfunction "2_8") (pintype "passive"))
      (node (ref "X2") (pin "15") (pinfunction "1_15") (pintype "passive"))
    )
    (net (code "49") (name "Net-(RN1B-2)") (class "Default")
      (node (ref "RN1") (pin "7") (pinfunction "2_7") (pintype "passive"))
      (node (ref "X2") (pin "14") (pinfunction "1_14") (pintype "passive"))
    )
    (net (code "50") (name "Net-(RN1C-2)") (class "Default")
      (node (ref "RN1") (pin "6") (pinfunction "2_6") (pintype "passive"))
      (node (ref "X2") (pin "13") (pinfunction "1_13") (pintype "passive"))
    )
    (net (code "51") (name "Net-(RN1D-2)") (class "Default")
      (node (ref "RN1") (pin "5") (pinfunction "2_5") (pintype "passive"))
      (node (ref "X2") (pin "9") (pinfunction "1_9") (pintype "passive"))
    )
    (net (code "52") (name "Net-(X2N-1)") (class "Default")
      (node (ref "X2") (pin "21") (pinfunction "1_21") (pintype "passive"))
      (node (ref "X2") (pin "22") (pinfunction "1_22") (pintype "passive"))
    )
    (net (code "53") (name "PREL0") (class "Default")
      (node (ref "IC1") (pin "39") (pinfunction "PB3_39") (pintype "bidirectional"))
      (node (ref "Q1") (pin "1") (pinfunction "G_1") (pintype "passive"))
      (node (ref "R2") (pin "1") (pinfunction "1_1") (pintype "passive"))
    )
    (net (code "54") (name "PREL1") (class "Default")
      (node (ref "IC1") (pin "40") (pinfunction "PB4_40") (pintype "bidirectional"))
      (node (ref "Q2") (pin "1") (pinfunction "G_1") (pintype "passive"))
      (node (ref "R3") (pin "1") (pinfunction "1_1") (pintype "passive"))
    )
    (net (code "55") (name "PREL2") (class "Default")
      (node (ref "IC1") (pin "41") (pinfunction "PB5_41") (pintype "bidirectional"))
      (node (ref "Q3") (pin "1") (pinfunction "G_1") (pintype "passive"))
      (node (ref "R4") (pin "1") (pinfunction "1_1") (pintype "passive"))
    )
    (net (code "56") (name "PREL3") (class "Default")
      (node (ref "IC1") (pin "42") (pinfunction "PB6_42") (pintype "bidirectional"))
      (node (ref "Q4") (pin "1") (pinfunction "G_1") (pintype "passive"))
      (node (ref "R5") (pin "1") (pinfunction "1_1") (pintype "passive"))
    )
    (net (code "57") (name "PREL4") (class "Default")
      (node (ref "IC1") (pin "43") (pinfunction "PB7_43") (pintype "bidirectional"))
      (node (ref "Q5") (pin "1") (pinfunction "G_1") (pintype "passive"))
      (node (ref "R6") (pin "1") (pinfunction "1_1") (pintype "passive"))
    )
    (net (code "58") (name "PREL5") (class "Default")
      (node (ref "IC1") (pin "45") (pinfunction "PB8_45") (pintype "bidirectional"))
      (node (ref "Q6") (pin "1") (pinfunction "G_1") (pintype "passive"))
      (node (ref "R7") (pin "1") (pinfunction "1_1") (pintype "passive"))
    )
    (net (code "59") (name "SWCLK") (class "Default")
      (node (ref "IC1") (pin "37") (pinfunction "PA14_37") (pintype "bidirectional"))
      (node (ref "X1") (pin "2") (pinfunction "1_2") (pintype "passive"))
    )
    (net (code "60") (name "SWDIO") (class "Default")
      (node (ref "IC1") (pin "34") (pinfunction "PA13_34") (pintype "bidirectional"))
      (node (ref "X1") (pin "4") (pinfunction "1_4") (pintype "passive"))
    )
    (net (code "61") (name "UART_RX") (class "Default")
      (node (ref "IC1") (pin "31") (pinfunction "PA10_31") (pintype "bidirectional"))
      (node (ref "X2") (pin "27") (pinfunction "1_27") (pintype "passive"))
    )
    (net (code "62") (name "UART_TX") (class "Default")
      (node (ref "IC1") (pin "30") (pinfunction "PA9_30") (pintype "bidirectional"))
      (node (ref "IC2") (pin "2") (pinfunction "I_2") (pintype "input"))
      (node (ref "RN2") (pin "1") (pinfunction "1_1") (pintype "passive"))
    )
    (net (code "63") (name "unconnected-(IC1-PA0-Pad10)") (class "Default")
      (node (ref "IC1") (pin "10") (pinfunction "PA0_10") (pintype "bidirectional"))
    )
    (net (code "64") (name "unconnected-(IC1-PA1-Pad11)") (class "Default")
      (node (ref "IC1") (pin "11") (pinfunction "PA1_11") (pintype "bidirectional"))
    )
    (net (code "65") (name "unconnected-(IC1-PA2-Pad12)") (class "Default")
      (node (ref "IC1") (pin "12") (pinfunction "PA2_12") (pintype "bidirectional"))
    )
    (net (code "66") (name "unconnected-(IC1-PA3-Pad13)") (class "Default")
      (node (ref "IC1") (pin "13") (pinfunction "PA3_13") (pintype "bidirectional"))
    )
    (net (code "67") (name "unconnected-(IC1-PA4-Pad14)") (class "Default")
      (node (ref "IC1") (pin "14") (pinfunction "PA4_14") (pintype "bidirectional"))
    )
    (net (code "68") (name "unconnected-(IC1-PA5-Pad15)") (class "Default")
      (node (ref "IC1") (pin "15") (pinfunction "PA5_15") (pintype "bidirectional"))
    )
    (net (code "69") (name "unconnected-(IC1-PA6-Pad16)") (class "Default")
      (node (ref "IC1") (pin "16") (pinfunction "PA6_16") (pintype "bidirectional"))
    )
    (net (code "70") (name "unconnected-(IC1-PA7-Pad17)") (class "Default")
      (node (ref "IC1") (pin "17") (pinfunction "PA7_17") (pintype "bidirectional"))
    )
    (net (code "71") (name "unconnected-(IC1-PA8-Pad29)") (class "Default")
      (node (ref "IC1") (pin "29") (pinfunction "PA8_29") (pintype "bidirectional"))
    )
    (net (code "72") (name "unconnected-(IC1-PA11-Pad32)") (class "Default")
      (node (ref "IC1") (pin "32") (pinfunction "PA11_32") (pintype "bidirectional"))
    )
    (net (code "73") (name "unconnected-(IC1-PA15-Pad38)") (class "Default")
      (node (ref "IC1") (pin "38") (pinfunction "PA15_38") (pintype "bidirectional"))
    )
    (net (code "74") (name "unconnected-(IC1-PB0-Pad18)") (class "Default")
      (node (ref "IC1") (pin "18") (pinfunction "PB0_18") (pintype "bidirectional"))
    )
    (net (code "75") (name "unconnected-(IC1-PB1-Pad19)") (class "Default")
      (node (ref "IC1") (pin "19") (pinfunction "PB1_19") (pintype "bidirectional"))
    )
    (net (code "76") (name "unconnected-(IC1-PB2-Pad20)") (class "Default")
      (node (ref "IC1") (pin "20") (pinfunction "PB2_20") (pintype "bidirectional"))
    )
    (net (code "77") (name "unconnected-(IC1-PB9-Pad46)") (class "Default")
      (node (ref "IC1") (pin "46") (pinfunction "PB9_46") (pintype "bidirectional"))
    )
    (net (code "78") (name "unconnected-(IC1-PB10-Pad21)") (class "Default")
      (node (ref "IC1") (pin "21") (pinfunction "PB10_21") (pintype "bidirectional"))
    )
    (net (code "79") (name "unconnected-(IC1-PB11-Pad22)") (class "Default")
      (node (ref "IC1") (pin "22") (pinfunction "PB11_22") (pintype "bidirectional"))
    )
    (net (code "80") (name "unconnected-(IC1-PC13-Pad2)") (class "Default")
      (node (ref "IC1") (pin "2") (pinfunction "PC13_2") (pintype "bidirectional"))
    )
    (net (code "81") (name "unconnected-(IC1-PC14-OSC32_IN-Pad3)") (class "Default")
      (node (ref "IC1") (pin "3") (pinfunction "PC14-OSC32_IN_3") (pintype "bidirectional"))
    )
    (net (code "82") (name "unconnected-(IC1-PC15-OSC32_OUT-Pad4)") (class "Default")
      (node (ref "IC1") (pin "4") (pinfunction "PC15-OSC32_OUT_4") (pintype "bidirectional"))
    )
    (net (code "83") (name "unconnected-(IC1-PF0-OSC_IN-Pad5)") (class "Default")
      (node (ref "IC1") (pin "5") (pinfunction "PF0-OSC_IN_5") (pintype "bidirectional"))
    )
    (net (code "84") (name "unconnected-(IC1-PF1-OSC_OUT-Pad6)") (class "Default")
      (node (ref "IC1") (pin "6") (pinfunction "PF1-OSC_OUT_6") (pintype "bidirectional"))
    )
    (net (code "85") (name "unconnected-(IC1-PF6-Pad35)") (class "Default")
      (node (ref "IC1") (pin "35") (pinfunction "PF6_35") (pintype "bidirectional"))
    )
    (net (code "86") (name "unconnected-(IC1-PF7-Pad36)") (class "Default")
      (node (ref "IC1") (pin "36") (pinfunction "PF7_36") (pintype "bidirectional"))
    )
    (net (code "87") (name "unconnected-(K1A-S-Pad12A)") (class "Default")
      (node (ref "K1") (pin "12A") (pinfunction "S_12A") (pintype "passive"))
    )
    (net (code "88") (name "unconnected-(K1B-S-Pad12B)") (class "Default")
      (node (ref "K1") (pin "12B") (pinfunction "S_12B") (pintype "passive"))
    )
    (net (code "89") (name "unconnected-(K6A-S-Pad12A)") (class "Default")
      (node (ref "K6") (pin "12A") (pinfunction "S_12A") (pintype "passive"))
    )
    (net (code "90") (name "unconnected-(K6B-S-Pad12B)") (class "Default")
      (node (ref "K6") (pin "12B") (pinfunction "S_12B") (pintype "passive"))
    )
    (net (code "91") (name "unconnected-(X2-Pad1)") (class "Default")
      (node (ref "X2") (pin "1") (pinfunction "1_1") (pintype "passive"))
    )
    (net (code "92") (name "unconnected-(X2D-1-Pad12)") (class "Default")
      (node (ref "X2") (pin "12") (pinfunction "1_12") (pintype "passive"))
    )
    (net (code "93") (name "unconnected-(X2L-1-Pad2)") (class "Default")
      (node (ref "X2") (pin "2") (pinfunction "1_2") (pintype "passive"))
    )
    (net (code "94") (name "unconnected-(X2V-1-Pad3)") (class "Default")
      (node (ref "X2") (pin "3") (pinfunction "1_3") (pintype "passive"))
    )
    (net (code "95") (name "unconnected-(X2Y-1-Pad6)") (class "Default")
      (node (ref "X2") (pin "6") (pinfunction "1_6") (pintype "passive"))
    )
  )
)
